# Main.net
KiCad netlist of a schematic drawn in Altium Designer
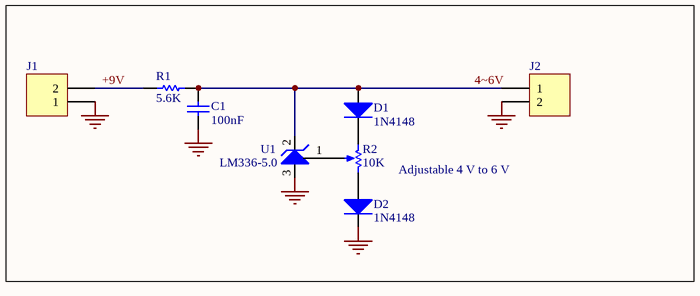
[diagram p0: Main.SchDoc]

(export (version "E")
  (design (tool "Eeschema 10.0.6"))
  (components
    (comp (ref "C1")
      (value "100nF")
      (footprint "CAPNTO2.54-3.05x1.78A")
      (description "Capacitor")
      (fields
        (field (name "MANUFACTURER") "Generic Components")
        (field (name "Comment") "Cap")
        (field (name "PUBLISHER") "Altium Limited")
      )
      (libsource (lib "Miscellaneous Devices") (part "Cap"))
    )
    (comp (ref "D1")
      (value "1N4148")
      (footprint "DIODE0.4_Glass")
      (description "Default Diode")
      (fields (field (name "MANUFACTURER") "Generic Components") (field (name "PUBLISHER") "Altium Limited"))
      (libsource (lib "Miscellaneous Devices") (part "Diode"))
    )
    (comp (ref "D2")
      (value "1N4148")
      (footprint "DIODE0.4_Glass")
      (description "Default Diode")
      (fields (field (name "MANUFACTURER") "Generic Components") (field (name "PUBLISHER") "Altium Limited"))
      (libsource (lib "Miscellaneous Devices") (part "Diode"))
    )
    (comp (ref "J1")
      (value "2PIN")
      (footprint "HDR1X2")
      (description "Header, 2-Pin")
      (fields (field (name "MANUFACTURER") "Generic Components") (field (name "PUBLISHER") "Altium Limited"))
      (libsource (lib "") (part "Header 2_1"))
    )
    (comp (ref "J2")
      (value "2PIN")
      (footprint "HDR1X2")
      (description "Header, 2-Pin")
      (fields (field (name "MANUFACTURER") "Generic Components") (field (name "PUBLISHER") "Altium Limited"))
      (libsource (lib "Miscellaneous Connectors") (part "Header 2"))
    )
    (comp (ref "R1")
      (value "5.6K")
      (footprint "AXIAL-0.4")
      (description "Resistor")
      (fields (field (name "Comment") "Res1") (field (name "PUBLISHER") "Altium Limited"))
      (libsource (lib "Miscellaneous Devices") (part "Res1"))
    )
    (comp (ref "R2")
      (value "10K")
      (footprint "VR4_")
      (description "Potentiometer")
      (fields
        (field (name "MANUFACTURER") "Generic Components")
        (field (name "Comment") "POT")
        (field (name "PUBLISHER") "Altium Limited")
      )
      (libsource (lib "my Libraries") (part "RPot1"))
    )
    (comp (ref "U1")
      (value "LM336-5.0")
      (footprint "TO92C")
      (description "Programmable Shunt Regulator")
      (libsource (lib "my Libraries") (part "LM336"))
    )
  )
  (nets
    (net (code "1") (name "/+9V") (class "Default")
      (node (ref "J1") (pin "2") (pinfunction "2_2") (pintype "passive"))
      (node (ref "R1") (pin "2") (pinfunction "2_2") (pintype "passive"))
    )
    (net (code "2") (name "/4~6V") (class "Default")
      (node (ref "C1") (pin "1") (pinfunction "1_1") (pintype "passive"))
      (node (ref "D1") (pin "1") (pinfunction "A_1") (pintype "passive"))
      (node (ref "J2") (pin "1") (pinfunction "1_1") (pintype "passive"))
      (node (ref "R1") (pin "1") (pinfunction "1_1") (pintype "passive"))
      (node (ref "U1") (pin "2") (pinfunction "+_2") (pintype "passive"))
    )
    (net (code "3") (name "GND") (class "Default")
      (node (ref "C1") (pin "2") (pinfunction "2_2") (pintype "passive"))
      (node (ref "D2") (pin "2") (pinfunction "K_2") (pintype "passive"))
      (node (ref "J1") (pin "1") (pinfunction "1_1") (pintype "passive"))
      (node (ref "J2") (pin "2") (pinfunction "2_2") (pintype "passive"))
      (node (ref "U1") (pin "3") (pinfunction "-_3") (pintype "passive"))
    )
    (net (code "4") (name "Net-(D1-K)") (class "Default")
      (node (ref "D1") (pin "2") (pinfunction "K_2") (pintype "passive"))
      (node (ref "R2") (pin "2") (pinfunction "BOT_2") (pintype "passive"))
    )
    (net (code "5") (name "Net-(D2-A)") (class "Default")
      (node (ref "D2") (pin "1") (pinfunction "A_1") (pintype "passive"))
      (node (ref "R2") (pin "1") (pinfunction "TOP_1") (pintype "passive"))
    )
    (net (code "6") (name "Net-(R2-TAP)") (class "Default")
      (node (ref "R2") (pin "3") (pinfunction "TAP_3") (pintype "passive"))
      (node (ref "U1") (pin "1") (pinfunction "Adj_1") (pintype "passive"))
    )
  )
)
